# bilancia_smart_pezzi_ali.net
KiCad netlist of a schematic drawn in EAGLE
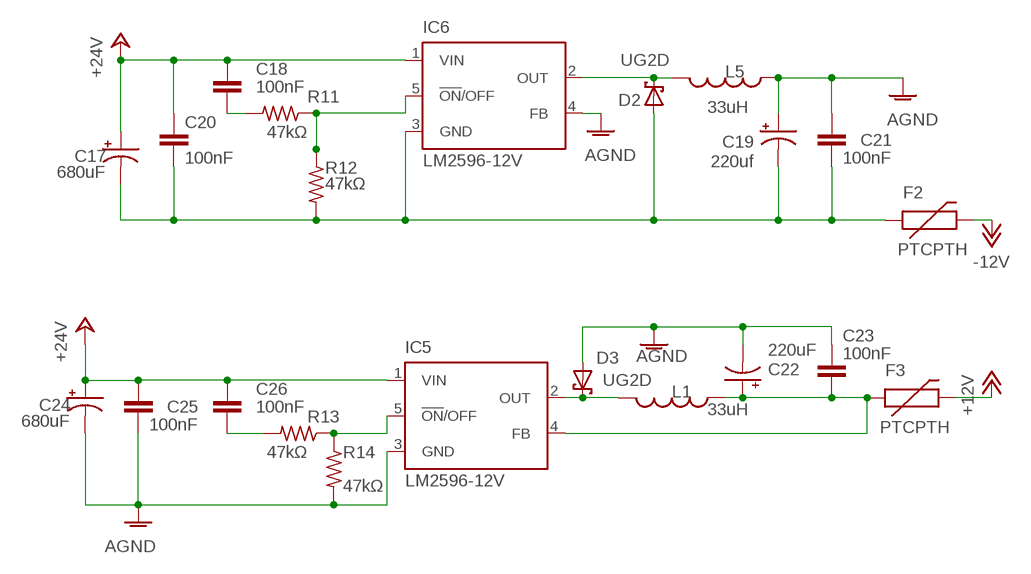
[diagram p0: schematic, sheet 1]

(export (version "E")
  (design (tool "Eeschema 10.0.6"))
  (components
    (comp (ref "C17")
      (value "680uF")
      (footprint "eagle-import:E5-8,5")
      (libsource (lib "eagle-import") (part "CPOL-USE5-8.5"))
    )
    (comp (ref "C18")
      (value "100nF")
      (footprint "eagle-import:C2.5-2")
      (libsource (lib "eagle-import") (part "C2.5/2"))
    )
    (comp (ref "C19")
      (value "220uf")
      (footprint "eagle-import:E5-8,5")
      (libsource (lib "eagle-import") (part "CPOL-USE5-8.5"))
    )
    (comp (ref "C20")
      (value "100nF")
      (footprint "eagle-import:C2.5-2")
      (libsource (lib "eagle-import") (part "C2.5/2"))
    )
    (comp (ref "C21")
      (value "100nF")
      (footprint "eagle-import:C2.5-2")
      (libsource (lib "eagle-import") (part "C2.5/2"))
    )
    (comp (ref "C22")
      (value "220uF")
      (footprint "eagle-import:E5-8,5")
      (libsource (lib "eagle-import") (part "CPOL-USE5-8.5"))
    )
    (comp (ref "C23")
      (value "100nF")
      (footprint "eagle-import:C2.5-2")
      (libsource (lib "eagle-import") (part "C2.5/2"))
    )
    (comp (ref "C24")
      (value "680uF")
      (footprint "eagle-import:E5-8,5")
      (libsource (lib "eagle-import") (part "CPOL-USE5-8.5"))
    )
    (comp (ref "C25")
      (value "100nF")
      (footprint "eagle-import:C2.5-2")
      (libsource (lib "eagle-import") (part "C2.5/2"))
    )
    (comp (ref "C26")
      (value "100nF")
      (footprint "eagle-import:C2.5-2")
      (libsource (lib "eagle-import") (part "C2.5/2"))
    )
    (comp (ref "D2")
      (value "UG2D")
      (footprint "eagle-import:DO41-7")
      (libsource (lib "eagle-import") (part "SCHOTTKY-DIODEDO41-7"))
    )
    (comp (ref "D3")
      (value "UG2D")
      (footprint "eagle-import:DO41-7")
      (libsource (lib "eagle-import") (part "SCHOTTKY-DIODEDO41-7"))
    )
    (comp (ref "F2")
      (value "PTCPTH")
      (footprint "eagle-import:PTC")
      (libsource (lib "eagle-import") (part "PTCPTH"))
    )
    (comp (ref "F3")
      (value "PTCPTH")
      (footprint "eagle-import:PTC")
      (libsource (lib "eagle-import") (part "PTCPTH"))
    )
    (comp (ref "IC5")
      (value "LM2596-12V")
      (footprint "eagle-import:T05D")
      (fields (field (name "MPN") "LM2596T-ADJ/LF02"))
      (libsource (lib "eagle-import") (part "LM2596T"))
    )
    (comp (ref "IC6")
      (value "LM2596-12V")
      (footprint "eagle-import:T05D")
      (fields (field (name "MPN") "LM2596T-ADJ/LF02"))
      (libsource (lib "eagle-import") (part "LM2596T"))
    )
    (comp (ref "L1")
      (value "33uH")
      (footprint "eagle-import:RLB0912")
      (libsource (lib "eagle-import") (part "INDUCTORRLB0912"))
    )
    (comp (ref "L5")
      (value "33uH")
      (footprint "eagle-import:RLB0912")
      (libsource (lib "eagle-import") (part "INDUCTORRLB0912"))
    )
    (comp (ref "R11")
      (value "47kΩ")
      (footprint "eagle-import:0207_2V")
      (libsource (lib "eagle-import") (part "R-US_0207/2V"))
    )
    (comp (ref "R12")
      (value "47kΩ")
      (footprint "eagle-import:0207_2V")
      (libsource (lib "eagle-import") (part "R-US_0207/2V"))
    )
    (comp (ref "R13")
      (value "47kΩ")
      (footprint "eagle-import:0207_2V")
      (libsource (lib "eagle-import") (part "R-US_0207/2V"))
    )
    (comp (ref "R14")
      (value "47kΩ")
      (footprint "eagle-import:0207_2V")
      (libsource (lib "eagle-import") (part "R-US_0207/2V"))
    )
  )
  (nets
    (net (code "1") (name "+12V") (class "Default")
      (node (ref "F3") (pin "P$2") (pinfunction "2_P$2") (pintype "bidirectional"))
    )
    (net (code "2") (name "+24V") (class "Default")
      (node (ref "C17") (pin "+") (pinfunction "+_+") (pintype "passive"))
      (node (ref "C18") (pin "1") (pinfunction "1_1") (pintype "passive"))
      (node (ref "C20") (pin "1") (pinfunction "1_1") (pintype "passive"))
      (node (ref "C24") (pin "+") (pinfunction "+_+") (pintype "passive"))
      (node (ref "C25") (pin "1") (pinfunction "1_1") (pintype "passive"))
      (node (ref "C26") (pin "1") (pinfunction "1_1") (pintype "passive"))
      (node (ref "IC5") (pin "1") (pinfunction "VIN_1") (pintype "input"))
      (node (ref "IC6") (pin "1") (pinfunction "VIN_1") (pintype "input"))
    )
    (net (code "3") (name "-12V") (class "Default")
      (node (ref "F2") (pin "P$2") (pinfunction "2_P$2") (pintype "bidirectional"))
    )
    (net (code "4") (name "AGND") (class "Default")
      (node (ref "C19") (pin "+") (pinfunction "+_+") (pintype "passive"))
      (node (ref "C21") (pin "1") (pinfunction "1_1") (pintype "passive"))
      (node (ref "C22") (pin "-") (pinfunction "-_-") (pintype "passive"))
      (node (ref "C23") (pin "2") (pinfunction "2_2") (pintype "passive"))
      (node (ref "C24") (pin "-") (pinfunction "-_-") (pintype "passive"))
      (node (ref "C25") (pin "2") (pinfunction "2_2") (pintype "passive"))
      (node (ref "D3") (pin "A") (pinfunction "A_A") (pintype "passive"))
      (node (ref "IC5") (pin "3") (pinfunction "GND_3") (pintype "power_in"))
      (node (ref "IC6") (pin "4") (pinfunction "FB_4") (pintype "input"))
      (node (ref "L5") (pin "1") (pinfunction "1_1") (pintype "passive"))
      (node (ref "R14") (pin "2") (pinfunction "2_2") (pintype "passive"))
    )
    (net (code "5") (name "Net-(C18-Pad2)") (class "Default")
      (node (ref "C18") (pin "2") (pinfunction "2_2") (pintype "passive"))
      (node (ref "R11") (pin "2") (pinfunction "2_2") (pintype "passive"))
    )
    (net (code "6") (name "Net-(C26-Pad2)") (class "Default")
      (node (ref "C26") (pin "2") (pinfunction "2_2") (pintype "passive"))
      (node (ref "R13") (pin "2") (pinfunction "2_2") (pintype "passive"))
    )
    (net (code "7") (name "Net-(F2-1)") (class "Default")
      (node (ref "C17") (pin "-") (pinfunction "-_-") (pintype "passive"))
      (node (ref "C19") (pin "-") (pinfunction "-_-") (pintype "passive"))
      (node (ref "C20") (pin "2") (pinfunction "2_2") (pintype "passive"))
      (node (ref "C21") (pin "2") (pinfunction "2_2") (pintype "passive"))
      (node (ref "D2") (pin "A") (pinfunction "A_A") (pintype "passive"))
      (node (ref "F2") (pin "P$1") (pinfunction "1_P$1") (pintype "bidirectional"))
      (node (ref "IC6") (pin "3") (pinfunction "GND_3") (pintype "power_in"))
      (node (ref "R12") (pin "2") (pinfunction "2_2") (pintype "passive"))
    )
    (net (code "8") (name "Net-(F3-1)") (class "Default")
      (node (ref "C22") (pin "+") (pinfunction "+_+") (pintype "passive"))
      (node (ref "C23") (pin "1") (pinfunction "1_1") (pintype "passive"))
      (node (ref "F3") (pin "P$1") (pinfunction "1_P$1") (pintype "bidirectional"))
      (node (ref "IC5") (pin "4") (pinfunction "FB_4") (pintype "input"))
      (node (ref "L1") (pin "1") (pinfunction "1_1") (pintype "passive"))
    )
    (net (code "9") (name "Net-(IC5-OUT)") (class "Default")
      (node (ref "D3") (pin "C") (pinfunction "C_C") (pintype "passive"))
      (node (ref "IC5") (pin "2") (pinfunction "OUT_2") (pintype "output"))
      (node (ref "L1") (pin "2") (pinfunction "2_2") (pintype "passive"))
    )
    (net (code "10") (name "Net-(IC5-~{ON}{slash}OFF)") (class "Default")
      (node (ref "IC5") (pin "5") (pinfunction "~{ON}/OFF_5") (pintype "input"))
      (node (ref "R13") (pin "1") (pinfunction "1_1") (pintype "passive"))
      (node (ref "R14") (pin "1") (pinfunction "1_1") (pintype "passive"))
    )
    (net (code "11") (name "Net-(IC6-OUT)") (class "Default")
      (node (ref "D2") (pin "C") (pinfunction "C_C") (pintype "passive"))
      (node (ref "IC6") (pin "2") (pinfunction "OUT_2") (pintype "output"))
      (node (ref "L5") (pin "2") (pinfunction "2_2") (pintype "passive"))
    )
    (net (code "12") (name "Net-(IC6-~{ON}{slash}OFF)") (class "Default")
      (node (ref "IC6") (pin "5") (pinfunction "~{ON}/OFF_5") (pintype "input"))
      (node (ref "R11") (pin "1") (pinfunction "1_1") (pintype "passive"))
      (node (ref "R12") (pin "1") (pinfunction "1_1") (pintype "passive"))
    )
  )
)
